# Onboard_IO.net
KiCad netlist of a schematic drawn in Altium Designer
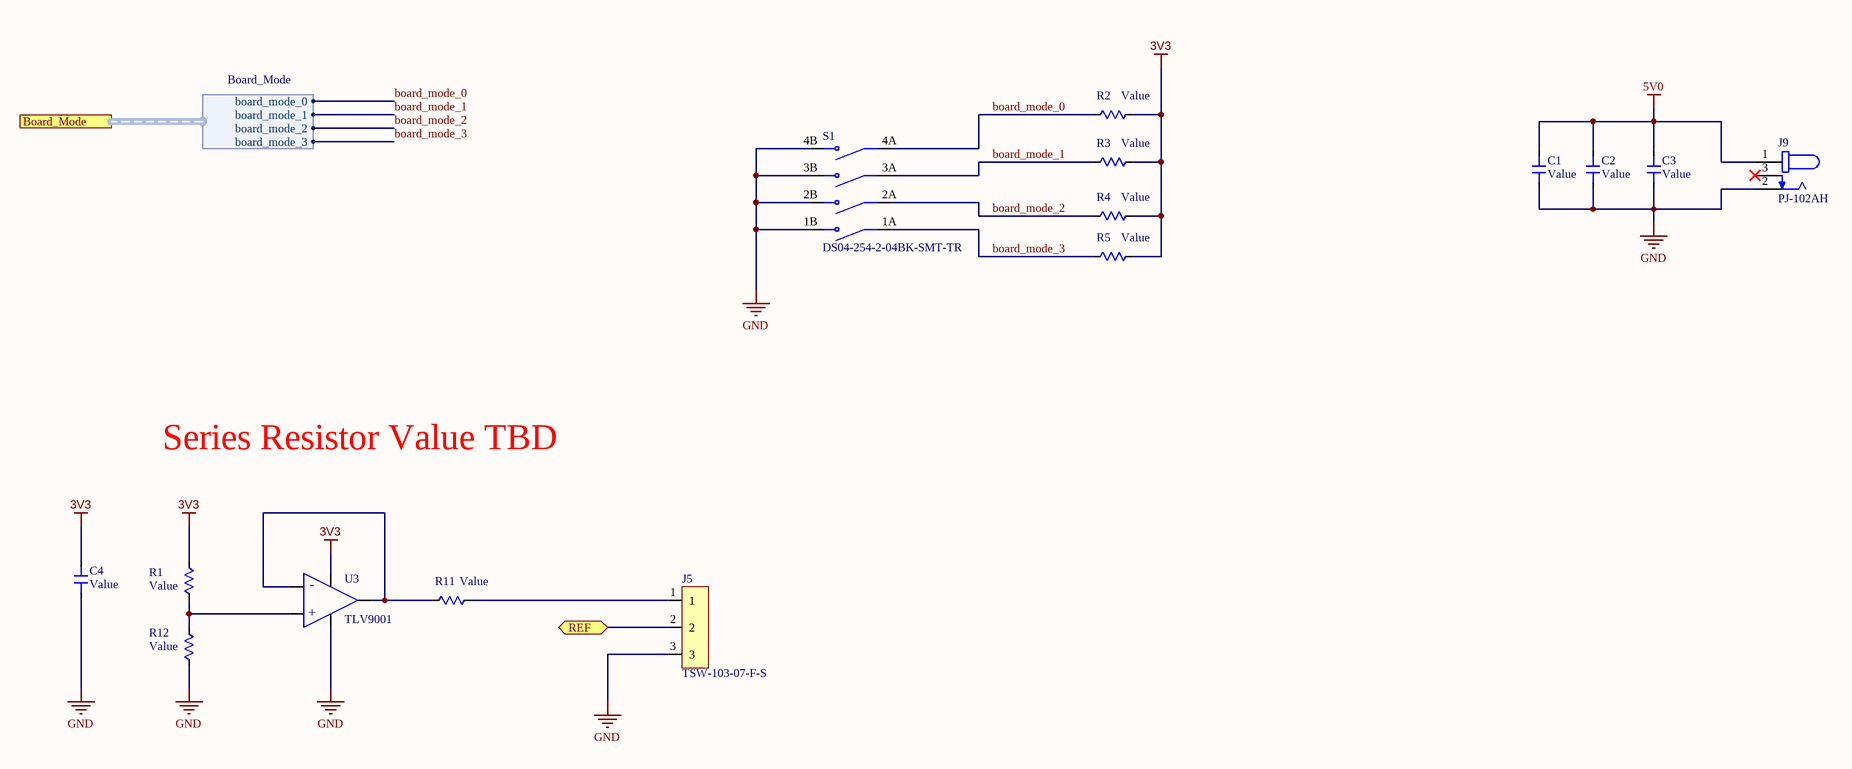
[diagram p0: Onboard_IO.SchDoc]

(export (version "E")
  (design (tool "Eeschema 10.0.6"))
  (components
    (comp (ref "C1")
      (value "Value")
      (footprint "0805_CAPACITOR")
      (description "Capacitor")
      (libsource (lib "UHDEMG") (part "Capacitor"))
    )
    (comp (ref "C2")
      (value "Value")
      (footprint "0603_CAPACITOR")
      (description "Capacitor")
      (libsource (lib "UHDEMG") (part "Capacitor"))
    )
    (comp (ref "C3")
      (value "Value")
      (footprint "0603_CAPACITOR")
      (description "Capacitor")
      (libsource (lib "UHDEMG") (part "Capacitor"))
    )
    (comp (ref "C4")
      (value "Value")
      (footprint "0603_CAPACITOR")
      (description "Capacitor")
      (libsource (lib "UHDEMG") (part "Capacitor"))
    )
    (comp (ref "J5")
      (value "TSW-103-07-F-S")
      (footprint "SMTC-TSW-103-07-X-S")
      (description "0.025\" SQ Post Header, Through-hole, Vertical, -55 to 125 degC, 2.54 mm Pitch, 3-Pin, Male, RoHS")
      (libsource (lib "UHDEMG") (part "CON_HEADER_1X3"))
    )
    (comp (ref "J9")
      (value "PJ-102AH")
      (footprint "CUI_PJ-102AH")
      (description "Power Barrel Connector Jack 2.00mm ID (0.079\"), 5.50mm OD (0.217\") Through Hole, Right Angle")
      (fields (field (name "MF") "Same Sky"))
      (libsource (lib "UHDEMG") (part "CON_PWR_24V_5A"))
    )
    (comp (ref "R1")
      (value "Value")
      (footprint "0603_RESISTOR")
      (description "Resistor")
      (libsource (lib "UHDEMG") (part "Resistor"))
    )
    (comp (ref "R2")
      (value "Value")
      (footprint "0603_RESISTOR")
      (description "Resistor")
      (libsource (lib "UHDEMG") (part "Resistor"))
    )
    (comp (ref "R3")
      (value "Value")
      (footprint "0603_RESISTOR")
      (description "Resistor")
      (libsource (lib "UHDEMG") (part "Resistor"))
    )
    (comp (ref "R4")
      (value "Value")
      (footprint "0603_RESISTOR")
      (description "Resistor")
      (libsource (lib "UHDEMG") (part "Resistor"))
    )
    (comp (ref "R5")
      (value "Value")
      (footprint "0603_RESISTOR")
      (description "Resistor")
      (libsource (lib "UHDEMG") (part "Resistor"))
    )
    (comp (ref "R11")
      (value "Value")
      (footprint "0603_RESISTOR")
      (description "Resistor")
      (libsource (lib "UHDEMG") (part "Resistor"))
    )
    (comp (ref "R12")
      (value "Value")
      (footprint "0603_RESISTOR")
      (description "Resistor")
      (libsource (lib "UHDEMG") (part "Resistor"))
    )
    (comp (ref "S1")
      (value "DS04-254-2-04BK-SMT-TR")
      (footprint "SW_DS04-254-2-04BK-SMT-TR")
      (description "Dip Switch SPST 4 Position Surface Mount Slide (Standard) Actuator 25mA 24VDC")
      (fields (field (name "MF") "Same Sky"))
      (libsource (lib "UHDEMG") (part "SW_DIP_4_SMT"))
    )
    (comp (ref "U3")
      (value "TLV9001")
      (footprint "SOT-353")
      (description "CMOS Amplifier 1 Circuit Rail-to-Rail SC-70-5\r\n1.8V - 5.5V")
      (libsource (lib "UHDEMG") (part "IC_OP_AMP_1CH"))
    )
  )
  (nets
    (net (code "2") (name "/REF") (class "Default")
      (node (ref "J5") (pin "2") (pinfunction "2_2") (pintype "passive"))
    )
    (net (code "3") (name "/board_mode_0") (class "Default")
      (node (ref "R2") (pin "1") (pinfunction "1_1") (pintype "passive"))
      (node (ref "S1") (pin "4A") (pinfunction "COM4_4A") (pintype "passive"))
    )
    (net (code "4") (name "/board_mode_1") (class "Default")
      (node (ref "R3") (pin "1") (pinfunction "1_1") (pintype "passive"))
      (node (ref "S1") (pin "3A") (pinfunction "COM3_3A") (pintype "passive"))
    )
    (net (code "5") (name "/board_mode_2") (class "Default")
      (node (ref "R4") (pin "1") (pinfunction "1_1") (pintype "passive"))
      (node (ref "S1") (pin "2A") (pinfunction "COM2_2A") (pintype "passive"))
    )
    (net (code "6") (name "/board_mode_3") (class "Default")
      (node (ref "R5") (pin "1") (pinfunction "1_1") (pintype "passive"))
      (node (ref "S1") (pin "1A") (pinfunction "COM1_1A") (pintype "passive"))
    )
    (net (code "8") (name "3V3") (class "Default")
      (node (ref "C4") (pin "2") (pinfunction "2_2") (pintype "passive"))
      (node (ref "R1") (pin "1") (pinfunction "1_1") (pintype "passive"))
      (node (ref "R2") (pin "2") (pinfunction "2_2") (pintype "passive"))
      (node (ref "R3") (pin "2") (pinfunction "2_2") (pintype "passive"))
      (node (ref "R4") (pin "2") (pinfunction "2_2") (pintype "passive"))
      (node (ref "R5") (pin "2") (pinfunction "2_2") (pintype "passive"))
      (node (ref "U3") (pin "5") (pinfunction "V+_5") (pintype "passive"))
    )
    (net (code "9") (name "5V0") (class "Default")
      (node (ref "C1") (pin "2") (pinfunction "2_2") (pintype "passive"))
      (node (ref "C2") (pin "2") (pinfunction "2_2") (pintype "passive"))
      (node (ref "C3") (pin "2") (pinfunction "2_2") (pintype "passive"))
      (node (ref "J9") (pin "1") (pinfunction "1_1") (pintype "passive"))
    )
    (net (code "10") (name "GND") (class "Default")
      (node (ref "C1") (pin "1") (pinfunction "1_1") (pintype "passive"))
      (node (ref "C2") (pin "1") (pinfunction "1_1") (pintype "passive"))
      (node (ref "C3") (pin "1") (pinfunction "1_1") (pintype "passive"))
      (node (ref "C4") (pin "1") (pinfunction "1_1") (pintype "passive"))
      (node (ref "J5") (pin "3") (pinfunction "3_3") (pintype "passive"))
      (node (ref "J9") (pin "2") (pinfunction "2_2") (pintype "passive"))
      (node (ref "R12") (pin "2") (pinfunction "2_2") (pintype "passive"))
      (node (ref "S1") (pin "1B") (pinfunction "NO1_1B") (pintype "passive"))
      (node (ref "S1") (pin "2B") (pinfunction "NO2_2B") (pintype "passive"))
      (node (ref "S1") (pin "3B") (pinfunction "NO3_3B") (pintype "passive"))
      (node (ref "S1") (pin "4B") (pinfunction "NO4_4B") (pintype "passive"))
      (node (ref "U3") (pin "2") (pinfunction "V-_2") (pintype "passive"))
    )
    (net (code "11") (name "Net-(J5-Pad1)") (class "Default")
      (node (ref "J5") (pin "1") (pinfunction "1_1") (pintype "passive"))
      (node (ref "R11") (pin "2") (pinfunction "2_2") (pintype "passive"))
    )
    (net (code "12") (name "Net-(U3-IN+)") (class "Default")
      (node (ref "R1") (pin "2") (pinfunction "2_2") (pintype "passive"))
      (node (ref "R12") (pin "1") (pinfunction "1_1") (pintype "passive"))
      (node (ref "U3") (pin "3") (pinfunction "IN+_3") (pintype "passive"))
    )
    (net (code "13") (name "Net-(U3-IN-)") (class "Default")
      (node (ref "R11") (pin "1") (pinfunction "1_1") (pintype "passive"))
      (node (ref "U3") (pin "1") (pinfunction "Out_1") (pintype "passive"))
      (node (ref "U3") (pin "4") (pinfunction "IN-_4") (pintype "passive"))
    )
    (net (code "14") (name "unconnected-(J9-Pad3)") (class "Default")
      (node (ref "J9") (pin "3") (pinfunction "3_3") (pintype "passive+no_connect"))
    )
  )
)
